# design.net
KiCad netlist of a schematic drawn in EasyEDA Pro
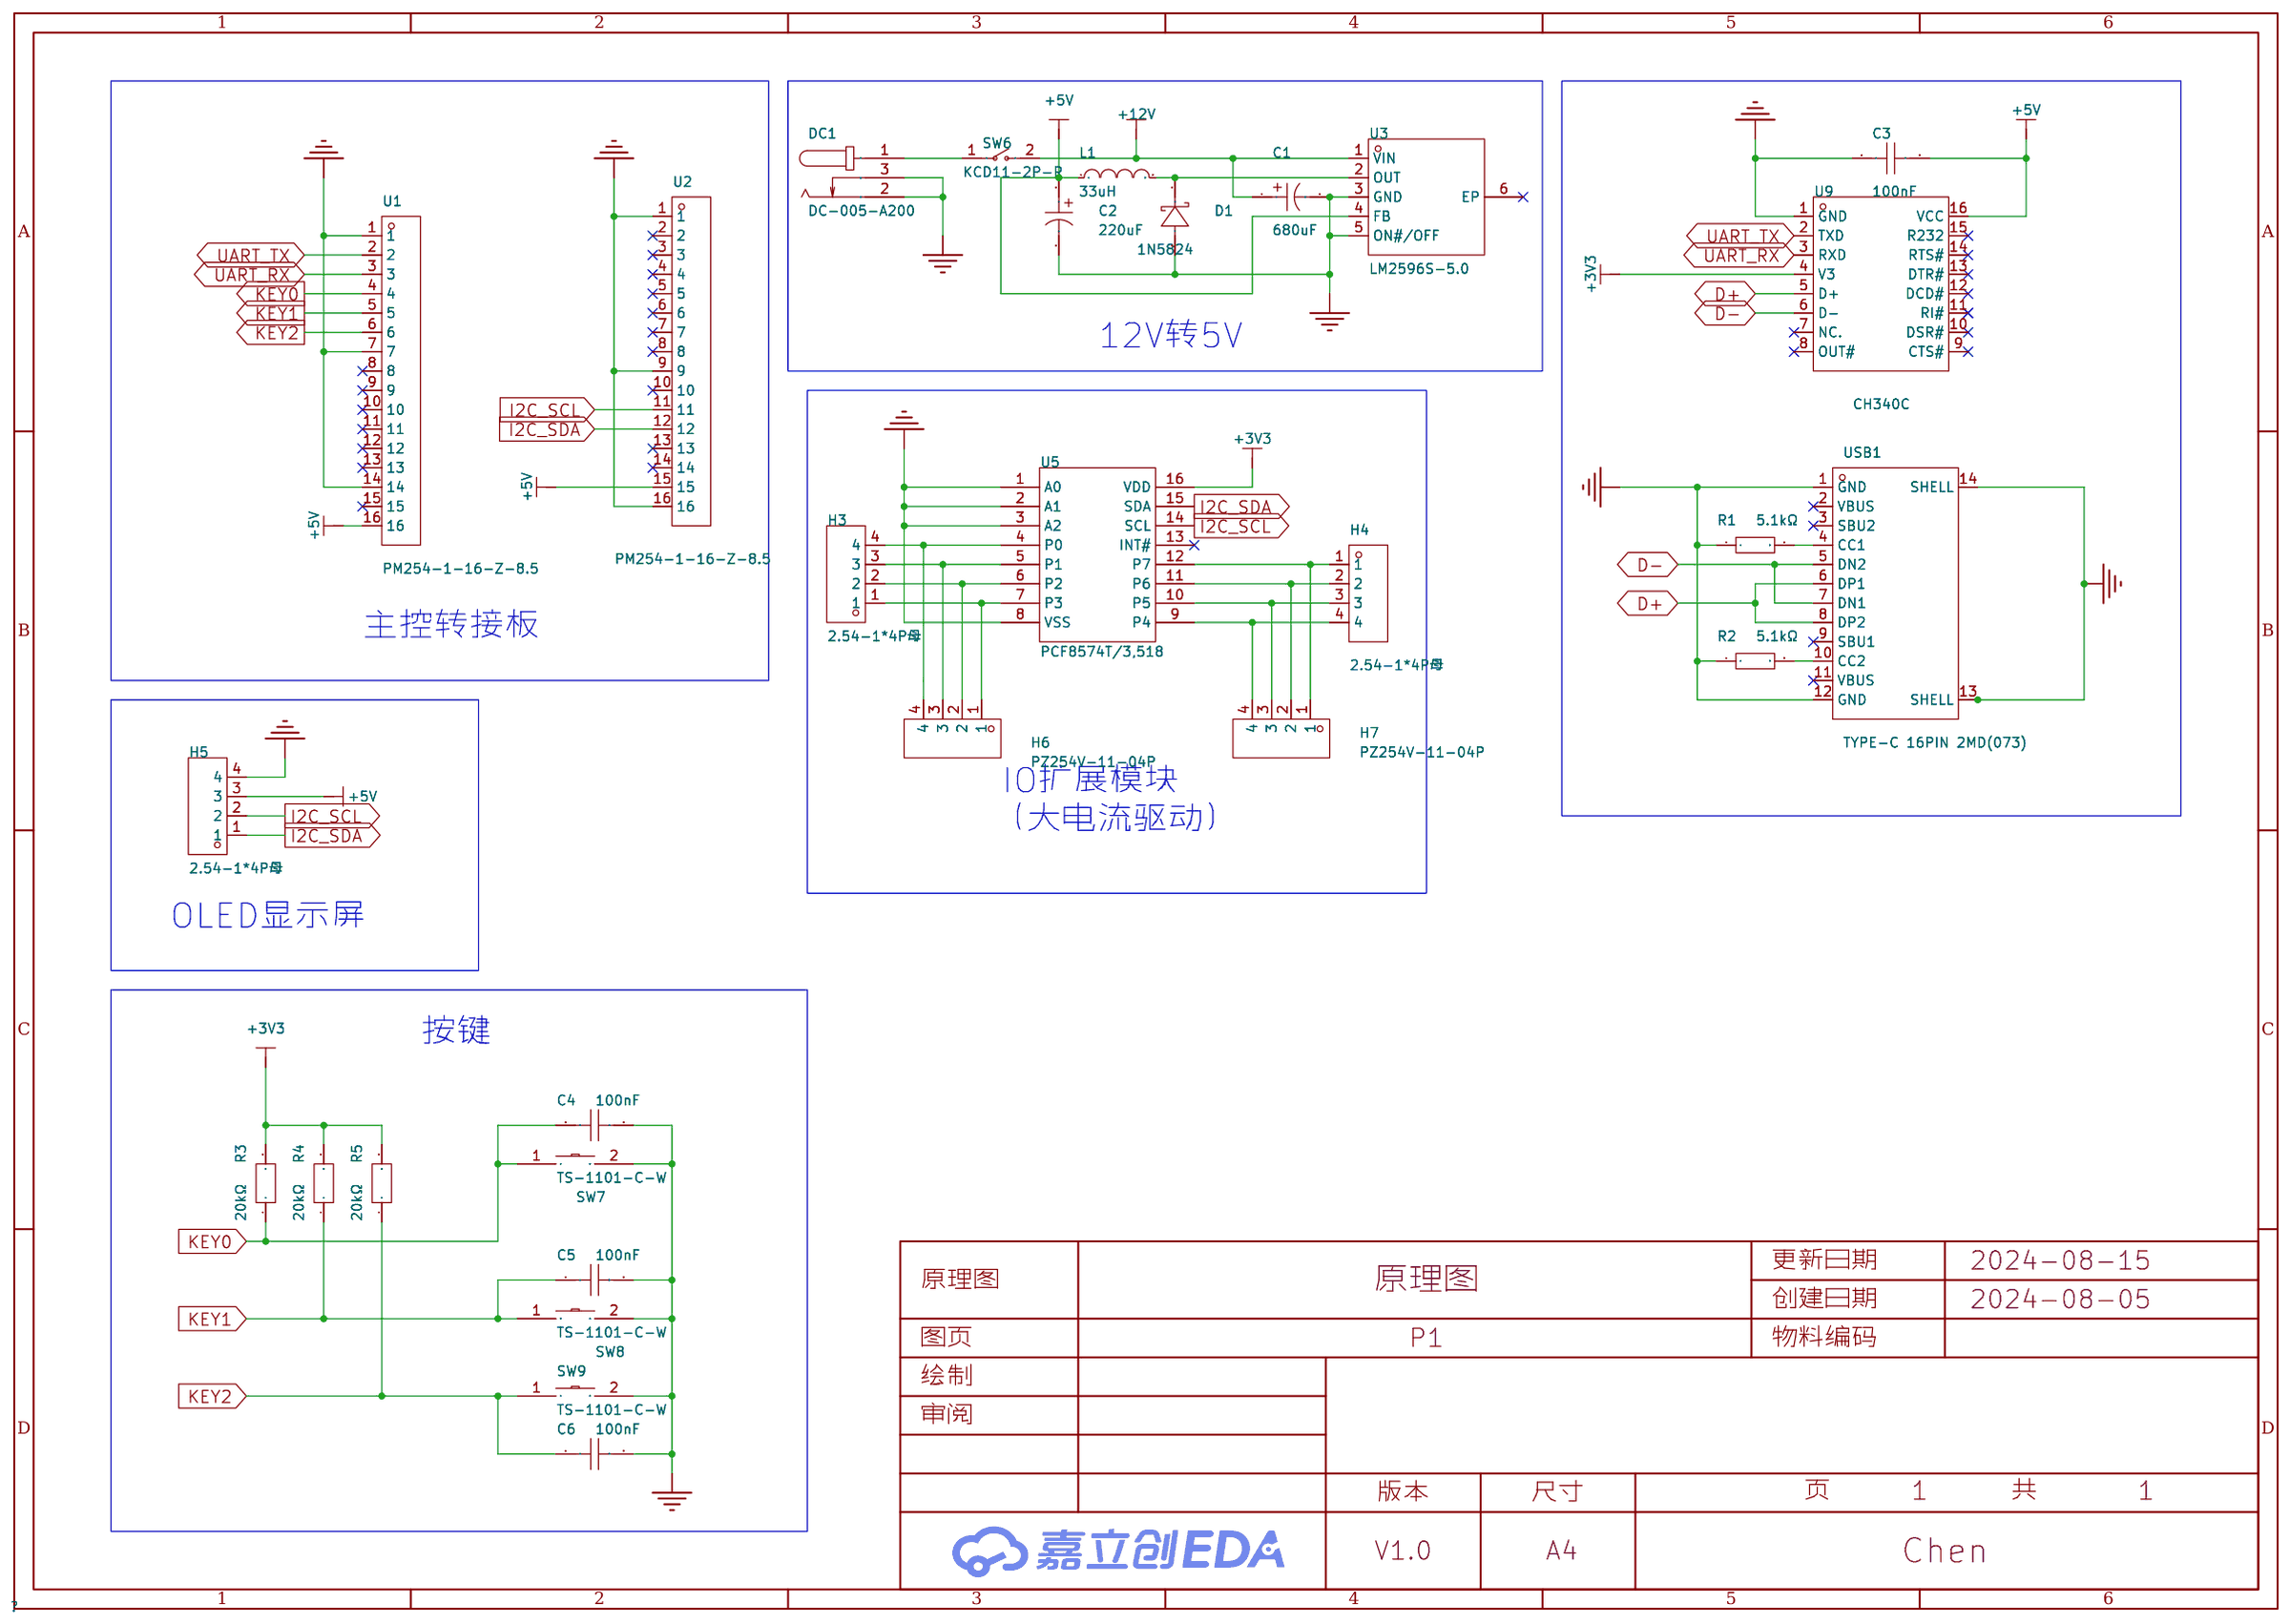
[diagram p0: schematic sheet]

(export (version "E")
  (design (tool "Eeschema 10.0.6"))
  (components
    (comp (ref "C1")
      (value "680uF")
      (footprint "easyedapro:CAP-TH_BD8.0-P3.50-D0.6-FD")
      (description "容值:680uF;精度:±20%;额定电压:10V;纹波电流:-;等效串联电阻:-;类型:-;")
      (fields (field (name "Manufacturer Part") "SPT1AM681F12OR") (field (name "Manufacturer") "Yunxing(云星)"))
      (libsource (lib "easyedapro") (part "SPT1AM681F12OR"))
    )
    (comp (ref "C2")
      (value "220uF")
      (footprint "easyedapro:CAP-SMD_BD6.3-L6.6-W6.6-LS7.4-FD")
      (description "容值:220uF;精度:±20%;额定电压:25V;纹波电流:150mA@120Hz;等效串联电阻:-;")
      (fields (field (name "Manufacturer Part") "RVT1E221M0607") (field (name "Manufacturer") "ROQANG(容强)"))
      (libsource (lib "easyedapro") (part "RVT1E221M0607_C2918361"))
    )
    (comp (ref "C3")
      (value "100nF")
      (footprint "easyedapro:CAP-TH_L7.2-W2.5-P5.00-D0.5")
      (description "容值:100nF;精度:±5%;额定电压:100V;介电材料:金属化聚酯膜电容;工作温度:-55°C~+125°C;")
      (fields
        (field (name "Manufacturer Part") "C242A104J2SC350")
        (field (name "Manufacturer") "faratronic(厦门法拉)")
      )
      (libsource (lib "easyedapro") (part "C242A104J2SC350"))
    )
    (comp (ref "C4")
      (value "100nF")
      (footprint "easyedapro:CAP-TH_L7.2-W2.5-P5.00-D0.5")
      (description "容值:100nF;精度:±5%;额定电压:100V;介电材料:金属化聚酯膜电容;工作温度:-55°C~+125°C;")
      (fields
        (field (name "Manufacturer Part") "C242A104J2SC350")
        (field (name "Manufacturer") "faratronic(厦门法拉)")
      )
      (libsource (lib "easyedapro") (part "C242A104J2SC350"))
    )
    (comp (ref "C5")
      (value "100nF")
      (footprint "easyedapro:CAP-TH_L7.2-W2.5-P5.00-D0.5")
      (description "容值:100nF;精度:±5%;额定电压:100V;介电材料:金属化聚酯膜电容;工作温度:-55°C~+125°C;")
      (fields
        (field (name "Manufacturer Part") "C242A104J2SC350")
        (field (name "Manufacturer") "faratronic(厦门法拉)")
      )
      (libsource (lib "easyedapro") (part "C242A104J2SC350"))
    )
    (comp (ref "C6")
      (value "100nF")
      (footprint "easyedapro:CAP-TH_L7.2-W2.5-P5.00-D0.5")
      (description "容值:100nF;精度:±5%;额定电压:100V;介电材料:金属化聚酯膜电容;工作温度:-55°C~+125°C;")
      (fields
        (field (name "Manufacturer Part") "C242A104J2SC350")
        (field (name "Manufacturer") "faratronic(厦门法拉)")
      )
      (libsource (lib "easyedapro") (part "C242A104J2SC350"))
    )
    (comp (ref "D1")
      (value "1N5824")
      (footprint "easyedapro:DO-27_BD5.3-L8.4-P12.40-D1.3-RD")
      (description "二极管配置:独立式;正向压降(Vf):550mV@5A;直流反向耐压(Vr):30V;平均整流电流(Io):5A;")
      (fields (field (name "Manufacturer") "FUXINSEMI(富芯森美)"))
      (libsource (lib "easyedapro") (part "1N5824_C7503125"))
    )
    (comp (ref "DC1")
      (value "DC-005-A200")
      (footprint "easyedapro:DC-IN-TH_DC-005-A200")
      (description "连接器类型:DC电源插座;安装方式:弯插;触点内径:2mm;触点外径:6.4mm;额定电流:3A;额定电压:30V;工作温度范围:-20°C~+70°C;")
      (fields (field (name "Manufacturer") "XUNPU(讯普)"))
      (libsource (lib "easyedapro") (part "DC-005-A200"))
    )
    (comp (ref "H3")
      (value "2.54-1*4P母")
      (footprint "easyedapro:HDR-TH_4P-P2.54-V-F")
      (fields (field (name "Manufacturer") "BOOMELE(博穆精密)"))
      (libsource (lib "easyedapro") (part "2.54-1*4P母"))
    )
    (comp (ref "H4")
      (value "2.54-1*4P母")
      (footprint "easyedapro:HDR-TH_4P-P2.54-V-F")
      (fields (field (name "Manufacturer") "BOOMELE(博穆精密)"))
      (libsource (lib "easyedapro") (part "2.54-1*4P母"))
    )
    (comp (ref "H5")
      (value "2.54-1*4P母")
      (footprint "easyedapro:HDR-TH_4P-P2.54-V-F")
      (fields (field (name "Manufacturer") "BOOMELE(博穆精密)"))
      (libsource (lib "easyedapro") (part "2.54-1*4P母"))
    )
    (comp (ref "H6")
      (value "PZ254V-11-04P")
      (footprint "easyedapro:HDR-TH_4P-P2.54-V-M")
      (fields (field (name "Manufacturer") "XFCN(兴飞)"))
      (libsource (lib "easyedapro") (part "PZ254V-11-04P_C2691448"))
    )
    (comp (ref "H7")
      (value "PZ254V-11-04P")
      (footprint "easyedapro:HDR-TH_4P-P2.54-V-M")
      (fields (field (name "Manufacturer") "XFCN(兴飞)"))
      (libsource (lib "easyedapro") (part "PZ254V-11-04P_C2691448"))
    )
    (comp (ref "L1")
      (value "33uH")
      (footprint "easyedapro:IND-SMD_L7.0-W6.6_FXL0630")
      (description "电感值:33uH;精度:±20%;额定电流:2A;饱和电流(Isat):2.5A;类型:一体成型电感;")
      (fields (field (name "Manufacturer Part") "FXL0630-330-M") (field (name "Manufacturer") "cjiang(长江微电)"))
      (libsource (lib "easyedapro") (part "FXL0630-330-M"))
    )
    (comp (ref "R1")
      (value "5.1kΩ")
      (footprint "easyedapro:R0603")
      (description "电阻类型:厚膜电阻;阻值:5.1kΩ;精度:±1%;功率:100mW;最大工作电压:75V;温度系数:±100ppm/°C;")
      (fields
        (field (name "Manufacturer Part") "0603WAF5101T5E")
        (field (name "Manufacturer") "UNI-ROYAL(厚声)")
      )
      (libsource (lib "easyedapro") (part "0603WAF5101T5E"))
    )
    (comp (ref "R2")
      (value "5.1kΩ")
      (footprint "easyedapro:R0603")
      (description "电阻类型:厚膜电阻;阻值:5.1kΩ;精度:±1%;功率:100mW;最大工作电压:75V;温度系数:±100ppm/°C;")
      (fields
        (field (name "Manufacturer Part") "0603WAF5101T5E")
        (field (name "Manufacturer") "UNI-ROYAL(厚声)")
      )
      (libsource (lib "easyedapro") (part "0603WAF5101T5E"))
    )
    (comp (ref "R3")
      (value "20kΩ")
      (footprint "easyedapro:R0603")
      (description "电阻类型:薄膜电阻;阻值:20kΩ;精度:±0.1%;功率:100mW;最大工作电压:75V;温度系数:±25ppm/°C;")
      (fields (field (name "Manufacturer Part") "RT0603BRD0720KL") (field (name "Manufacturer") "YAGEO(国巨)"))
      (libsource (lib "easyedapro") (part "RT0603BRD0720KL"))
    )
    (comp (ref "R4")
      (value "20kΩ")
      (footprint "easyedapro:R0603")
      (description "电阻类型:薄膜电阻;阻值:20kΩ;精度:±0.1%;功率:100mW;最大工作电压:75V;温度系数:±25ppm/°C;")
      (fields (field (name "Manufacturer Part") "RT0603BRD0720KL") (field (name "Manufacturer") "YAGEO(国巨)"))
      (libsource (lib "easyedapro") (part "RT0603BRD0720KL"))
    )
    (comp (ref "R5")
      (value "20kΩ")
      (footprint "easyedapro:R0603")
      (description "电阻类型:薄膜电阻;阻值:20kΩ;精度:±0.1%;功率:100mW;最大工作电压:75V;温度系数:±25ppm/°C;")
      (fields (field (name "Manufacturer Part") "RT0603BRD0720KL") (field (name "Manufacturer") "YAGEO(国巨)"))
      (libsource (lib "easyedapro") (part "RT0603BRD0720KL"))
    )
    (comp (ref "SW6")
      (value "KCD11-2P-R")
      (footprint "easyedapro:SW-TH_2P-L15.0-W10.5-P5.00_KCD11-2P-R")
      (description "带灯:无;引脚样式:焊片;额定电流:3A;额定电压(AC):250V;额定电压(DC):-;电路结构:单刀单掷;机械寿命:1万次;")
      (fields (field (name "Manufacturer") "SHOU HAN(首韩)"))
      (libsource (lib "easyedapro") (part "KCD11-2P-R"))
    )
    (comp (ref "SW7")
      (value "TS-1101-C-W")
      (footprint "easyedapro:SW-SMD_L6.0-W3.3-LS8.0")
      (fields (field (name "Manufacturer") "XKB Connectivity(中国星坤)"))
      (libsource (lib "easyedapro") (part "TS-1101-C-W"))
    )
    (comp (ref "SW8")
      (value "TS-1101-C-W")
      (footprint "easyedapro:SW-SMD_L6.0-W3.3-LS8.0")
      (fields (field (name "Manufacturer") "XKB Connectivity(中国星坤)"))
      (libsource (lib "easyedapro") (part "TS-1101-C-W"))
    )
    (comp (ref "SW9")
      (value "TS-1101-C-W")
      (footprint "easyedapro:SW-SMD_L6.0-W3.3-LS8.0")
      (fields (field (name "Manufacturer") "XKB Connectivity(中国星坤)"))
      (libsource (lib "easyedapro") (part "TS-1101-C-W"))
    )
    (comp (ref "U1")
      (value "PM254-1-16-Z-8.5")
      (footprint "easyedapro:HDR-TH_16P-P2.54-V-F-A")
      (fields (field (name "Manufacturer") "HCTL(华灿天禄)"))
      (libsource (lib "easyedapro") (part "PM254-1-16-Z-8.5"))
    )
    (comp (ref "U2")
      (value "PM254-1-16-Z-8.5")
      (footprint "easyedapro:HDR-TH_16P-P2.54-V-F-A")
      (fields (field (name "Manufacturer") "HCTL(华灿天禄)"))
      (libsource (lib "easyedapro") (part "PM254-1-16-Z-8.5"))
    )
    (comp (ref "U3")
      (value "LM2596S-5.0")
      (footprint "easyedapro:TO-263-5_L10.2-W8.9-P1.70-BR")
      (description "功能类型:降压型;输出类型:固定;输入电压:40V;输出电压:5V;输出电流(最大值):3A;")
      (fields (field (name "Manufacturer") "UMW(友台半导体)"))
      (libsource (lib "easyedapro") (part "LM2596S-5.0"))
    )
    (comp (ref "U5")
      (value "PCF8574T/3,518")
      (footprint "easyedapro:SOIC-16_L10.3-W7.5-P1.27-LS10.3-BL")
      (description "接口:I2C;I/O数量:8;时钟频率:100kHz;")
      (fields (field (name "Manufacturer") "NXP(恩智浦)"))
      (libsource (lib "easyedapro") (part "PCF8574T/3,518"))
    )
    (comp (ref "U9")
      (value "CH340C")
      (footprint "easyedapro:SOP-16_L10.0-W3.9-P1.27-LS6.0-BL")
      (description "应用功能:收发器;接口协议:USB 2.0;数据速率:2Mbps;")
      (fields (field (name "Manufacturer") "WCH(南京沁恒)"))
      (libsource (lib "easyedapro") (part "CH340C"))
    )
    (comp (ref "USB1")
      (value "TYPE-C 16PIN 2MD(073)")
      (footprint "easyedapro:USB-C-SMD_TYPE-C-6PIN-2MD-073")
      (description "连接器类型:Type-C;标准:-;公母:母;端口数量:1;触点数量:16P;安装方式:卧贴;额定电流 - 电源:5A;工作温度范围:-25°C~+85°C;")
      (fields (field (name "Manufacturer") "SHOU HAN(首韩)"))
      (libsource (lib "easyedapro") (part "TYPE-C 16PIN 2MD(073)"))
    )
  )
  (nets
    (net (code "1") (name "+3V3") (class "Default")
      (node (ref "R3") (pin "2") (pinfunction "2_2") (pintype "unspecified"))
      (node (ref "R4") (pin "2") (pinfunction "2_2") (pintype "unspecified"))
      (node (ref "R5") (pin "2") (pinfunction "2_2") (pintype "unspecified"))
      (node (ref "U5") (pin "16") (pinfunction "VDD_16") (pintype "unspecified"))
      (node (ref "U9") (pin "4") (pinfunction "V3_4") (pintype "unspecified"))
    )
    (net (code "2") (name "+5V") (class "Default")
      (node (ref "C2") (pin "1") (pinfunction "1_1") (pintype "input"))
      (node (ref "C3") (pin "2") (pinfunction "2_2") (pintype "unspecified"))
      (node (ref "H5") (pin "3") (pinfunction "3_3") (pintype "unspecified"))
      (node (ref "L1") (pin "1") (pinfunction "1_1") (pintype "unspecified"))
      (node (ref "U1") (pin "16") (pinfunction "16_16") (pintype "unspecified"))
      (node (ref "U2") (pin "15") (pinfunction "15_15") (pintype "unspecified"))
      (node (ref "U3") (pin "4") (pinfunction "FB_4") (pintype "unspecified"))
      (node (ref "U9") (pin "16") (pinfunction "VCC_16") (pintype "unspecified"))
    )
    (net (code "3") (name "+12V") (class "Default")
      (node (ref "C1") (pin "1") (pinfunction "1_1") (pintype "input"))
      (node (ref "SW6") (pin "2") (pinfunction "2_2") (pintype "unspecified"))
      (node (ref "U3") (pin "1") (pinfunction "VIN_1") (pintype "unspecified"))
    )
    (net (code "4") (name "D+") (class "Default")
      (node (ref "U9") (pin "5") (pinfunction "D+_5") (pintype "unspecified"))
      (node (ref "USB1") (pin "6") (pinfunction "DP1_6") (pintype "unspecified"))
      (node (ref "USB1") (pin "8") (pinfunction "DP2_8") (pintype "unspecified"))
    )
    (net (code "5") (name "D-") (class "Default")
      (node (ref "U9") (pin "6") (pinfunction "D-_6") (pintype "unspecified"))
      (node (ref "USB1") (pin "5") (pinfunction "DN2_5") (pintype "unspecified"))
      (node (ref "USB1") (pin "7") (pinfunction "DN1_7") (pintype "unspecified"))
    )
    (net (code "6") (name "GND") (class "Default")
      (node (ref "C1") (pin "2") (pinfunction "2_2") (pintype "input"))
      (node (ref "C2") (pin "2") (pinfunction "2_2") (pintype "input"))
      (node (ref "C3") (pin "1") (pinfunction "1_1") (pintype "unspecified"))
      (node (ref "C4") (pin "2") (pinfunction "2_2") (pintype "unspecified"))
      (node (ref "C5") (pin "2") (pinfunction "2_2") (pintype "unspecified"))
      (node (ref "C6") (pin "2") (pinfunction "2_2") (pintype "unspecified"))
      (node (ref "D1") (pin "2") (pinfunction "A_2") (pintype "unspecified"))
      (node (ref "DC1") (pin "2") (pinfunction "2_2") (pintype "unspecified"))
      (node (ref "DC1") (pin "3") (pinfunction "3_3") (pintype "unspecified"))
      (node (ref "H5") (pin "4") (pinfunction "4_4") (pintype "unspecified"))
      (node (ref "R1") (pin "1") (pinfunction "1_1") (pintype "input"))
      (node (ref "R2") (pin "1") (pinfunction "1_1") (pintype "input"))
      (node (ref "SW7") (pin "2") (pinfunction "2_2") (pintype "unspecified"))
      (node (ref "SW8") (pin "2") (pinfunction "2_2") (pintype "unspecified"))
      (node (ref "SW9") (pin "2") (pinfunction "2_2") (pintype "unspecified"))
      (node (ref "U1") (pin "1") (pinfunction "1_1") (pintype "unspecified"))
      (node (ref "U1") (pin "14") (pinfunction "14_14") (pintype "unspecified"))
      (node (ref "U1") (pin "7") (pinfunction "7_7") (pintype "unspecified"))
      (node (ref "U2") (pin "1") (pinfunction "1_1") (pintype "unspecified"))
      (node (ref "U2") (pin "16") (pinfunction "16_16") (pintype "unspecified"))
      (node (ref "U2") (pin "9") (pinfunction "9_9") (pintype "unspecified"))
      (node (ref "U3") (pin "3") (pinfunction "GND_3") (pintype "unspecified"))
      (node (ref "U3") (pin "5") (pinfunction "ON#/OFF_5") (pintype "unspecified"))
      (node (ref "U5") (pin "1") (pinfunction "A0_1") (pintype "unspecified"))
      (node (ref "U5") (pin "2") (pinfunction "A1_2") (pintype "unspecified"))
      (node (ref "U5") (pin "3") (pinfunction "A2_3") (pintype "unspecified"))
      (node (ref "U5") (pin "8") (pinfunction "VSS_8") (pintype "unspecified"))
      (node (ref "U9") (pin "1") (pinfunction "GND_1") (pintype "unspecified"))
      (node (ref "USB1") (pin "1") (pinfunction "GND_1") (pintype "unspecified"))
      (node (ref "USB1") (pin "12") (pinfunction "GND_12") (pintype "unspecified"))
      (node (ref "USB1") (pin "13") (pinfunction "SHELL_13") (pintype "unspecified"))
      (node (ref "USB1") (pin "14") (pinfunction "SHELL_14") (pintype "unspecified"))
    )
    (net (code "7") (name "I2C_SCL") (class "Default")
      (node (ref "H5") (pin "2") (pinfunction "2_2") (pintype "unspecified"))
      (node (ref "U2") (pin "11") (pinfunction "11_11") (pintype "unspecified"))
      (node (ref "U5") (pin "14") (pinfunction "SCL_14") (pintype "unspecified"))
    )
    (net (code "8") (name "I2C_SDA") (class "Default")
      (node (ref "H5") (pin "1") (pinfunction "1_1") (pintype "unspecified"))
      (node (ref "U2") (pin "12") (pinfunction "12_12") (pintype "unspecified"))
      (node (ref "U5") (pin "15") (pinfunction "SDA_15") (pintype "unspecified"))
    )
    (net (code "9") (name "KEY0") (class "Default")
      (node (ref "C4") (pin "1") (pinfunction "1_1") (pintype "unspecified"))
      (node (ref "R3") (pin "1") (pinfunction "1_1") (pintype "unspecified"))
      (node (ref "SW7") (pin "1") (pinfunction "1_1") (pintype "unspecified"))
      (node (ref "U1") (pin "4") (pinfunction "4_4") (pintype "unspecified"))
    )
    (net (code "10") (name "KEY1") (class "Default")
      (node (ref "C5") (pin "1") (pinfunction "1_1") (pintype "unspecified"))
      (node (ref "R4") (pin "1") (pinfunction "1_1") (pintype "unspecified"))
      (node (ref "SW8") (pin "1") (pinfunction "1_1") (pintype "unspecified"))
      (node (ref "U1") (pin "5") (pinfunction "5_5") (pintype "unspecified"))
    )
    (net (code "11") (name "KEY2") (class "Default")
      (node (ref "C6") (pin "1") (pinfunction "1_1") (pintype "unspecified"))
      (node (ref "R5") (pin "1") (pinfunction "1_1") (pintype "unspecified"))
      (node (ref "SW9") (pin "1") (pinfunction "1_1") (pintype "unspecified"))
      (node (ref "U1") (pin "6") (pinfunction "6_6") (pintype "unspecified"))
    )
    (net (code "12") (name "Net-(D1-K)") (class "Default")
      (node (ref "D1") (pin "1") (pinfunction "K_1") (pintype "unspecified"))
      (node (ref "L1") (pin "2") (pinfunction "2_2") (pintype "unspecified"))
      (node (ref "U3") (pin "2") (pinfunction "OUT_2") (pintype "unspecified"))
    )
    (net (code "13") (name "Net-(DC1-Pad1)") (class "Default")
      (node (ref "DC1") (pin "1") (pinfunction "1_1") (pintype "unspecified"))
      (node (ref "SW6") (pin "1") (pinfunction "1_1") (pintype "unspecified"))
    )
    (net (code "14") (name "Net-(U5-P0)") (class "Default")
      (node (ref "H3") (pin "4") (pinfunction "4_4") (pintype "unspecified"))
      (node (ref "H6") (pin "4") (pinfunction "4_4") (pintype "unspecified"))
      (node (ref "U5") (pin "4") (pinfunction "P0_4") (pintype "unspecified"))
    )
    (net (code "15") (name "Net-(U5-P1)") (class "Default")
      (node (ref "H3") (pin "3") (pinfunction "3_3") (pintype "unspecified"))
      (node (ref "H6") (pin "3") (pinfunction "3_3") (pintype "unspecified"))
      (node (ref "U5") (pin "5") (pinfunction "P1_5") (pintype "unspecified"))
    )
    (net (code "16") (name "Net-(U5-P2)") (class "Default")
      (node (ref "H3") (pin "2") (pinfunction "2_2") (pintype "unspecified"))
      (node (ref "H6") (pin "2") (pinfunction "2_2") (pintype "unspecified"))
      (node (ref "U5") (pin "6") (pinfunction "P2_6") (pintype "unspecified"))
    )
    (net (code "17") (name "Net-(U5-P3)") (class "Default")
      (node (ref "H3") (pin "1") (pinfunction "1_1") (pintype "unspecified"))
      (node (ref "H6") (pin "1") (pinfunction "1_1") (pintype "unspecified"))
      (node (ref "U5") (pin "7") (pinfunction "P3_7") (pintype "unspecified"))
    )
    (net (code "18") (name "Net-(U5-P4)") (class "Default")
      (node (ref "H4") (pin "4") (pinfunction "4_4") (pintype "unspecified"))
      (node (ref "H7") (pin "4") (pinfunction "4_4") (pintype "unspecified"))
      (node (ref "U5") (pin "9") (pinfunction "P4_9") (pintype "unspecified"))
    )
    (net (code "19") (name "Net-(U5-P5)") (class "Default")
      (node (ref "H4") (pin "3") (pinfunction "3_3") (pintype "unspecified"))
      (node (ref "H7") (pin "3") (pinfunction "3_3") (pintype "unspecified"))
      (node (ref "U5") (pin "10") (pinfunction "P5_10") (pintype "unspecified"))
    )
    (net (code "20") (name "Net-(U5-P6)") (class "Default")
      (node (ref "H4") (pin "2") (pinfunction "2_2") (pintype "unspecified"))
      (node (ref "H7") (pin "2") (pinfunction "2_2") (pintype "unspecified"))
      (node (ref "U5") (pin "11") (pinfunction "P6_11") (pintype "unspecified"))
    )
    (net (code "21") (name "Net-(U5-P7)") (class "Default")
      (node (ref "H4") (pin "1") (pinfunction "1_1") (pintype "unspecified"))
      (node (ref "H7") (pin "1") (pinfunction "1_1") (pintype "unspecified"))
      (node (ref "U5") (pin "12") (pinfunction "P7_12") (pintype "unspecified"))
    )
    (net (code "22") (name "Net-(USB1-CC1)") (class "Default")
      (node (ref "R1") (pin "2") (pinfunction "2_2") (pintype "input"))
      (node (ref "USB1") (pin "4") (pinfunction "CC1_4") (pintype "unspecified"))
    )
    (net (code "23") (name "Net-(USB1-CC2)") (class "Default")
      (node (ref "R2") (pin "2") (pinfunction "2_2") (pintype "input"))
      (node (ref "USB1") (pin "10") (pinfunction "CC2_10") (pintype "unspecified"))
    )
    (net (code "24") (name "UART_RX") (class "Default")
      (node (ref "U1") (pin "3") (pinfunction "3_3") (pintype "unspecified"))
      (node (ref "U9") (pin "3") (pinfunction "RXD_3") (pintype "unspecified"))
    )
    (net (code "25") (name "UART_TX") (class "Default")
      (node (ref "U1") (pin "2") (pinfunction "2_2") (pintype "unspecified"))
      (node (ref "U9") (pin "2") (pinfunction "TXD_2") (pintype "unspecified"))
    )
    (net (code "26") (name "unconnected-(U1-Pad8)") (class "Default")
      (node (ref "U1") (pin "8") (pinfunction "8_8") (pintype "unspecified+no_connect"))
    )
    (net (code "27") (name "unconnected-(U1-Pad9)") (class "Default")
      (node (ref "U1") (pin "9") (pinfunction "9_9") (pintype "unspecified+no_connect"))
    )
    (net (code "28") (name "unconnected-(U1-Pad10)") (class "Default")
      (node (ref "U1") (pin "10") (pinfunction "10_10") (pintype "unspecified+no_connect"))
    )
    (net (code "29") (name "unconnected-(U1-Pad11)") (class "Default")
      (node (ref "U1") (pin "11") (pinfunction "11_11") (pintype "unspecified+no_connect"))
    )
    (net (code "30") (name "unconnected-(U1-Pad12)") (class "Default")
      (node (ref "U1") (pin "12") (pinfunction "12_12") (pintype "unspecified+no_connect"))
    )
    (net (code "31") (name "unconnected-(U1-Pad13)") (class "Default")
      (node (ref "U1") (pin "13") (pinfunction "13_13") (pintype "unspecified+no_connect"))
    )
    (net (code "32") (name "unconnected-(U1-Pad15)") (class "Default")
      (node (ref "U1") (pin "15") (pinfunction "15_15") (pintype "unspecified+no_connect"))
    )
    (net (code "33") (name "unconnected-(U2-Pad2)") (class "Default")
      (node (ref "U2") (pin "2") (pinfunction "2_2") (pintype "unspecified+no_connect"))
    )
    (net (code "34") (name "unconnected-(U2-Pad3)") (class "Default")
      (node (ref "U2") (pin "3") (pinfunction "3_3") (pintype "unspecified+no_connect"))
    )
    (net (code "35") (name "unconnected-(U2-Pad4)") (class "Default")
      (node (ref "U2") (pin "4") (pinfunction "4_4") (pintype "unspecified+no_connect"))
    )
    (net (code "36") (name "unconnected-(U2-Pad5)") (class "Default")
      (node (ref "U2") (pin "5") (pinfunction "5_5") (pintype "unspecified+no_connect"))
    )
    (net (code "37") (name "unconnected-(U2-Pad6)") (class "Default")
      (node (ref "U2") (pin "6") (pinfunction "6_6") (pintype "unspecified+no_connect"))
    )
    (net (code "38") (name "unconnected-(U2-Pad7)") (class "Default")
      (node (ref "U2") (pin "7") (pinfunction "7_7") (pintype "unspecified+no_connect"))
    )
    (net (code "39") (name "unconnected-(U2-Pad8)") (class "Default")
      (node (ref "U2") (pin "8") (pinfunction "8_8") (pintype "unspecified+no_connect"))
    )
    (net (code "40") (name "unconnected-(U2-Pad10)") (class "Default")
      (node (ref "U2") (pin "10") (pinfunction "10_10") (pintype "unspecified+no_connect"))
    )
    (net (code "41") (name "unconnected-(U2-Pad13)") (class "Default")
      (node (ref "U2") (pin "13") (pinfunction "13_13") (pintype "unspecified+no_connect"))
    )
    (net (code "42") (name "unconnected-(U2-Pad14)") (class "Default")
      (node (ref "U2") (pin "14") (pinfunction "14_14") (pintype "unspecified+no_connect"))
    )
    (net (code "43") (name "unconnected-(U3-EP-Pad6)") (class "Default")
      (node (ref "U3") (pin "6") (pinfunction "EP_6") (pintype "unspecified+no_connect"))
    )
    (net (code "44") (name "unconnected-(U5-INT#-Pad13)") (class "Default")
      (node (ref "U5") (pin "13") (pinfunction "INT#_13") (pintype "unspecified+no_connect"))
    )
    (net (code "45") (name "unconnected-(U9-CTS#-Pad9)") (class "Default")
      (node (ref "U9") (pin "9") (pinfunction "CTS#_9") (pintype "unspecified+no_connect"))
    )
    (net (code "46") (name "unconnected-(U9-DCD#-Pad12)") (class "Default")
      (node (ref "U9") (pin "12") (pinfunction "DCD#_12") (pintype "unspecified+no_connect"))
    )
    (net (code "47") (name "unconnected-(U9-DSR#-Pad10)") (class "Default")
      (node (ref "U9") (pin "10") (pinfunction "DSR#_10") (pintype "unspecified+no_connect"))
    )
    (net (code "48") (name "unconnected-(U9-DTR#-Pad13)") (class "Default")
      (node (ref "U9") (pin "13") (pinfunction "DTR#_13") (pintype "unspecified+no_connect"))
    )
    (net (code "49") (name "unconnected-(U9-NC.-Pad7)") (class "Default")
      (node (ref "U9") (pin "7") (pinfunction "NC._7") (pintype "unspecified+no_connect"))
    )
    (net (code "50") (name "unconnected-(U9-OUT#-Pad8)") (class "Default")
      (node (ref "U9") (pin "8") (pinfunction "OUT#_8") (pintype "unspecified+no_connect"))
    )
    (net (code "51") (name "unconnected-(U9-R232-Pad15)") (class "Default")
      (node (ref "U9") (pin "15") (pinfunction "R232_15") (pintype "unspecified+no_connect"))
    )
    (net (code "52") (name "unconnected-(U9-RI#-Pad11)") (class "Default")
      (node (ref "U9") (pin "11") (pinfunction "RI#_11") (pintype "unspecified+no_connect"))
    )
    (net (code "53") (name "unconnected-(U9-RTS#-Pad14)") (class "Default")
      (node (ref "U9") (pin "14") (pinfunction "RTS#_14") (pintype "unspecified+no_connect"))
    )
    (net (code "54") (name "unconnected-(USB1-SBU1-Pad9)") (class "Default")
      (node (ref "USB1") (pin "9") (pinfunction "SBU1_9") (pintype "unspecified+no_connect"))
    )
    (net (code "55") (name "unconnected-(USB1-SBU2-Pad3)") (class "Default")
      (node (ref "USB1") (pin "3") (pinfunction "SBU2_3") (pintype "unspecified+no_connect"))
    )
    (net (code "56") (name "unconnected-(USB1-VBUS-Pad2)") (class "Default")
      (node (ref "USB1") (pin "2") (pinfunction "VBUS_2") (pintype "unspecified+no_connect"))
    )
    (net (code "57") (name "unconnected-(USB1-VBUS-Pad11)") (class "Default")
      (node (ref "USB1") (pin "11") (pinfunction "VBUS_11") (pintype "unspecified+no_connect"))
    )
  )
)
